# pwm555.net
KiCad netlist of a schematic drawn in EAGLE
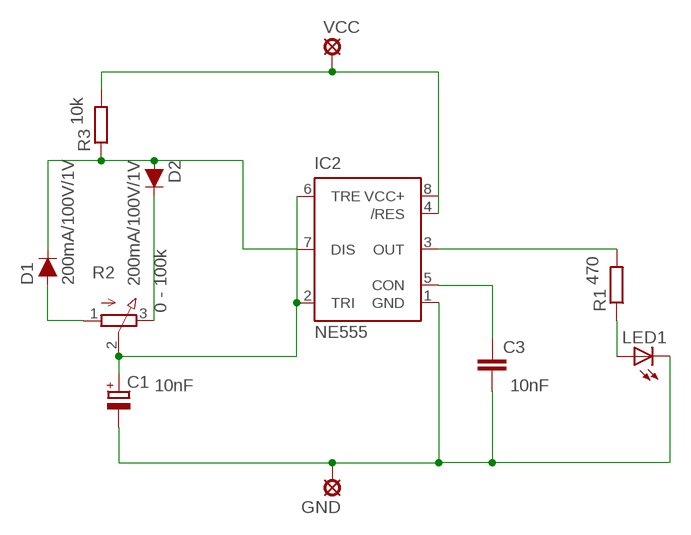
[diagram p0: schematic, sheet 1]

(export (version "E")
  (design (tool "Eeschema 10.0.6"))
  (components
    (comp (ref "C1")
      (value "CPOL-EUE2.5-6")
      (footprint "eagle-import:E2,5-6")
      (fields (field (name "C1") "10nF"))
      (libsource (lib "eagle-import") (part "CPOL-EUE2.5-6"))
    )
    (comp (ref "C3")
      (value "C-EU025-024X044")
      (footprint "eagle-import:C025-024X044")
      (fields (field (name "C2") "10nF"))
      (libsource (lib "eagle-import") (part "C-EU025-024X044"))
    )
    (comp (ref "D1")
      (value "200mA/100V/1V")
      (footprint "eagle-import:DIODE-1N4148")
      (libsource (lib "eagle-import") (part "DIODE-1N4148"))
    )
    (comp (ref "D2")
      (value "200mA/100V/1V")
      (footprint "eagle-import:DIODE-1N4148")
      (libsource (lib "eagle-import") (part "DIODE-1N4148"))
    )
    (comp (ref "GND")
      (value "LSP10")
      (footprint "eagle-import:LSP10")
      (libsource (lib "eagle-import") (part "LSP10"))
    )
    (comp (ref "IC2")
      (value "NE555")
      (footprint "eagle-import:DIL-08")
      (fields (field (name "MF") "Arrow Electronics") (field (name "MPN") "NE555N"))
      (libsource (lib "eagle-import") (part "NE555"))
    )
    (comp (ref "LED1")
      (value "LED5MM")
      (footprint "eagle-import:LED5MM")
      (libsource (lib "eagle-import") (part "LED5MM"))
    )
    (comp (ref "R1")
      (value "R-EU_0207/10")
      (footprint "eagle-import:0207_10")
      (fields (field (name "R6") "470"))
      (libsource (lib "eagle-import") (part "R-EU_0207/10"))
    )
    (comp (ref "R2")
      (value "3RP/1610N")
      (footprint "eagle-import:3RP_1610N")
      (fields (field (name "POT1") "0 - 100k"))
      (libsource (lib "eagle-import") (part "3RP/1610N"))
    )
    (comp (ref "R3")
      (value "R-EU_0207/10")
      (footprint "eagle-import:0207_10")
      (fields (field (name "R4") "10k"))
      (libsource (lib "eagle-import") (part "R-EU_0207/10"))
    )
    (comp (ref "VCC")
      (value "LSP10")
      (footprint "eagle-import:LSP10")
      (libsource (lib "eagle-import") (part "LSP10"))
    )
  )
  (nets
    (net (code "1") (name "Net-(IC2-CON)") (class "Default")
      (node (ref "C3") (pin "1") (pinfunction "1_1") (pintype "passive"))
      (node (ref "IC2") (pin "5") (pinfunction "CON_5") (pintype "input"))
    )
    (net (code "2") (name "Net-(IC2-DIS)") (class "Default")
      (node (ref "D1") (pin "C") (pinfunction "C_C") (pintype "passive"))
      (node (ref "D2") (pin "A") (pinfunction "A_A") (pintype "passive"))
      (node (ref "IC2") (pin "7") (pinfunction "DIS_7") (pintype "input"))
      (node (ref "R3") (pin "1") (pinfunction "1_1") (pintype "passive"))
    )
    (net (code "3") (name "Net-(IC2-GND)") (class "Default")
      (node (ref "C1") (pin "-") (pinfunction "-_-") (pintype "passive"))
      (node (ref "C3") (pin "2") (pinfunction "2_2") (pintype "passive"))
      (node (ref "GND") (pin "MP") (pinfunction "MP_MP") (pintype "passive"))
      (node (ref "IC2") (pin "1") (pinfunction "GND_1") (pintype "power_in"))
      (node (ref "LED1") (pin "K") (pinfunction "C_K") (pintype "passive"))
    )
    (net (code "4") (name "Net-(IC2-OUT)") (class "Default")
      (node (ref "IC2") (pin "3") (pinfunction "OUT_3") (pintype "output"))
      (node (ref "R1") (pin "2") (pinfunction "2_2") (pintype "passive"))
    )
    (net (code "5") (name "Net-(IC2-TRE)") (class "Default")
      (node (ref "C1") (pin "+") (pinfunction "+_+") (pintype "passive"))
      (node (ref "IC2") (pin "2") (pinfunction "TRI_2") (pintype "input"))
      (node (ref "IC2") (pin "6") (pinfunction "TRE_6") (pintype "input"))
      (node (ref "R2") (pin "2") (pinfunction "S_2") (pintype "passive"))
    )
    (net (code "6") (name "Net-(IC2-VCC+)") (class "Default")
      (node (ref "IC2") (pin "4") (pinfunction "/RES_4") (pintype "input"))
      (node (ref "IC2") (pin "8") (pinfunction "VCC+_8") (pintype "power_in"))
      (node (ref "R3") (pin "2") (pinfunction "2_2") (pintype "passive"))
      (node (ref "VCC") (pin "MP") (pinfunction "MP_MP") (pintype "passive"))
    )
    (net (code "7") (name "Net-(LED1-PadA)") (class "Default")
      (node (ref "LED1") (pin "A") (pinfunction "A_A") (pintype "passive"))
      (node (ref "R1") (pin "1") (pinfunction "1_1") (pintype "passive"))
    )
    (net (code "8") (name "Net-(R2-A)") (class "Default")
      (node (ref "D1") (pin "A") (pinfunction "A_A") (pintype "passive"))
      (node (ref "R2") (pin "1") (pinfunction "A_1") (pintype "passive"))
    )
    (net (code "9") (name "Net-(R2-E)") (class "Default")
      (node (ref "D2") (pin "C") (pinfunction "C_C") (pintype "passive"))
      (node (ref "R2") (pin "3") (pinfunction "E_3") (pintype "passive"))
    )
  )
)
